# astable_multivibrator.net
KiCad netlist of a schematic drawn in EAGLE
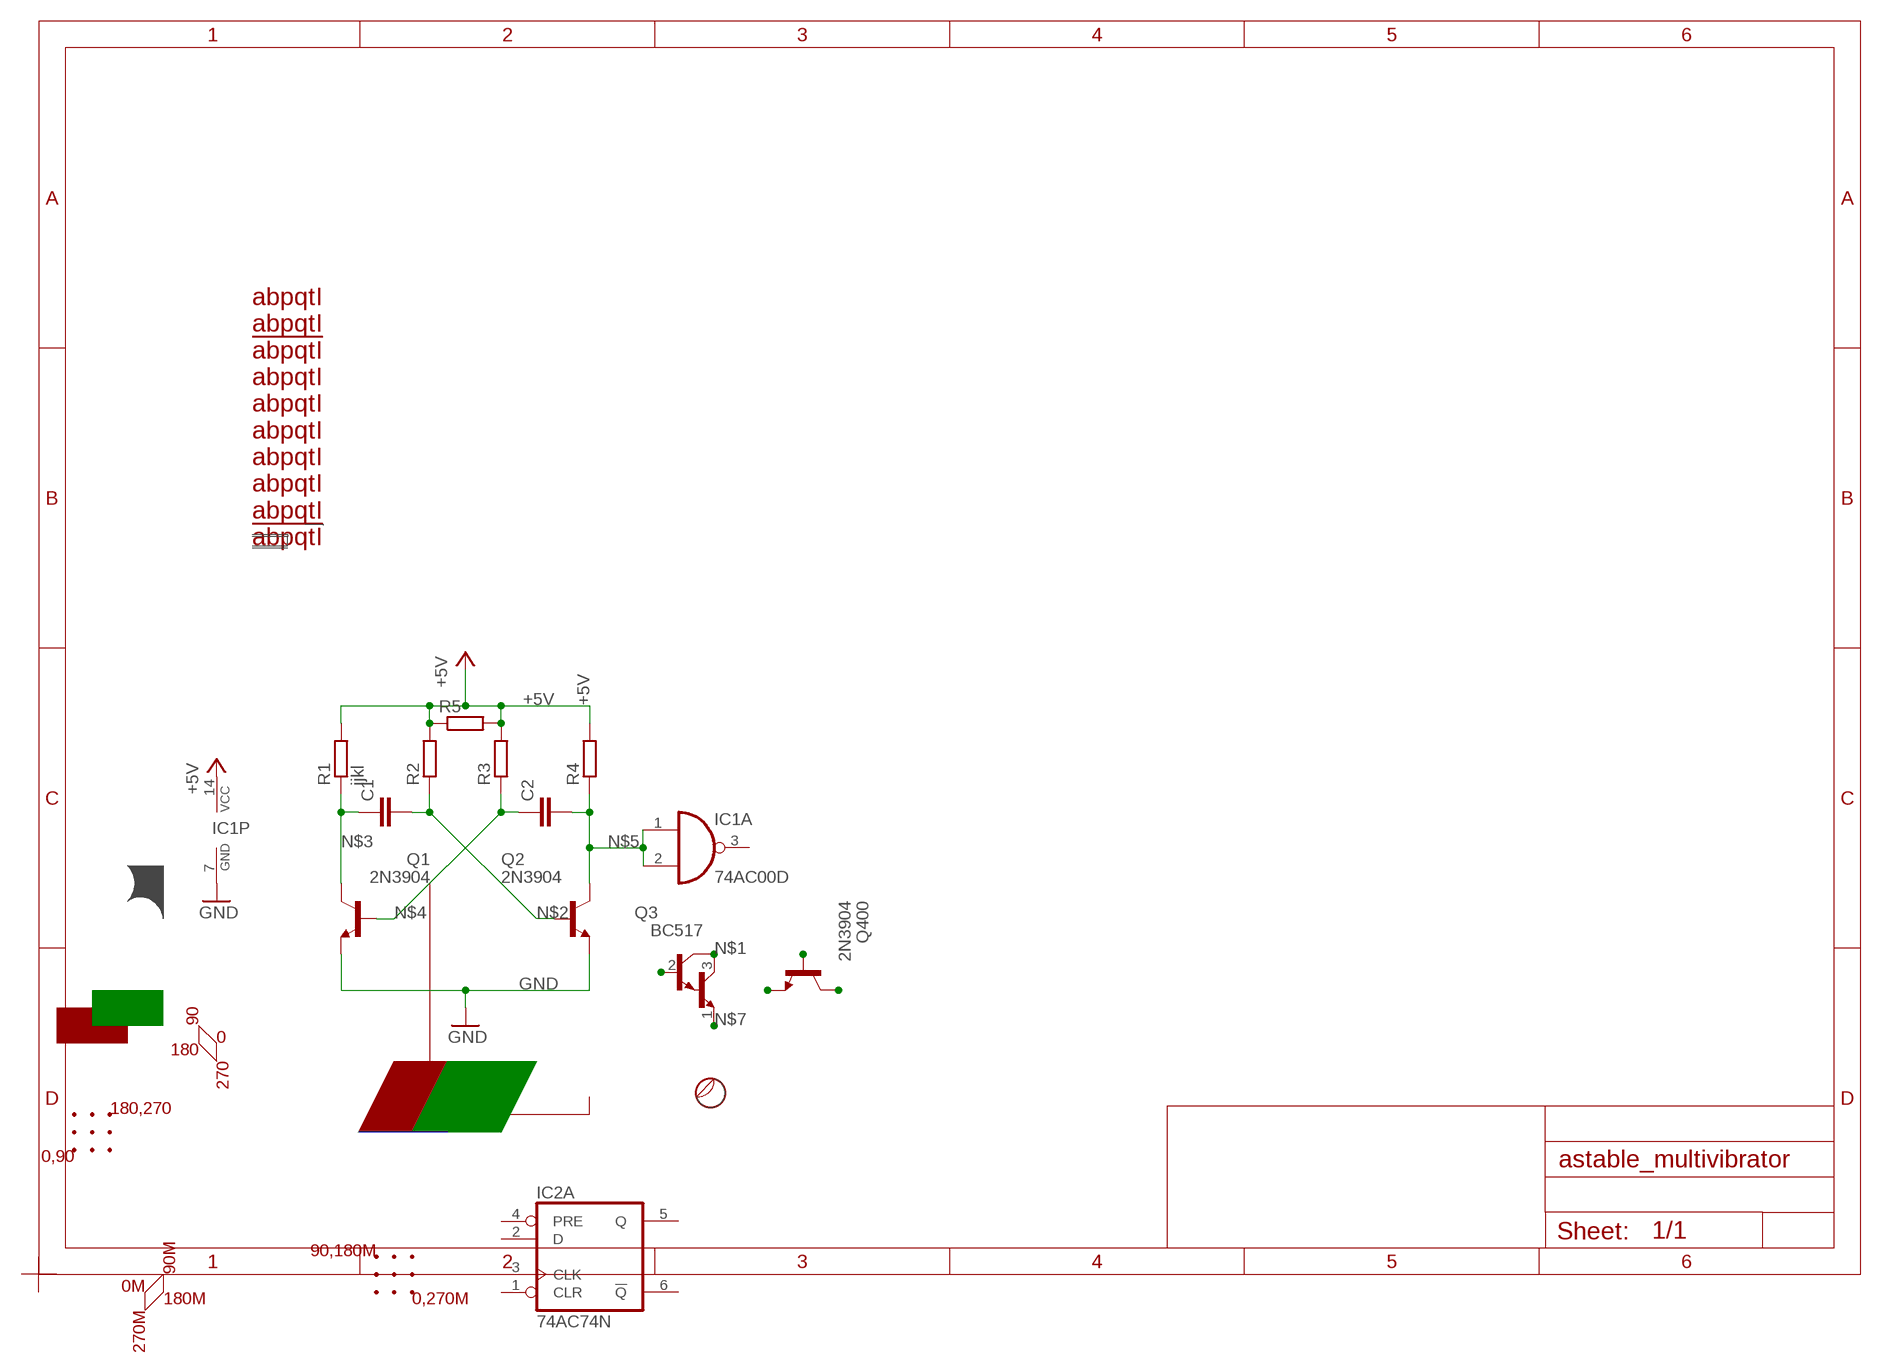
[diagram p0: schematic, sheet 1]

(export (version "E")
  (design (tool "Eeschema 10.0.6"))
  (components
    (comp (ref "C1")
      (value "C-EU025-024X044")
      (footprint "eagle-import:C025-024X044")
      (libsource (lib "eagle-import") (part "C-EU025-024X044"))
    )
    (comp (ref "C2")
      (value "C-EU025-024X044")
      (footprint "eagle-import:C025-024X044")
      (libsource (lib "eagle-import") (part "C-EU025-024X044"))
    )
    (comp (ref "IC1")
      (value "74AC00D")
      (footprint "eagle-import:SO14")
      (libsource (lib "eagle-import") (part "7400DAC"))
    )
    (comp (ref "IC2")
      (value "74AC74N")
      (footprint "eagle-import:DIL14")
      (libsource (lib "eagle-import") (part "7474NAC"))
    )
    (comp (ref "Q1")
      (value "2N3904")
      (footprint "eagle-import:TO92")
      (libsource (lib "eagle-import") (part "2N3904"))
    )
    (comp (ref "Q2")
      (value "2N3904")
      (footprint "eagle-import:TO92")
      (libsource (lib "eagle-import") (part "2N3904"))
    )
    (comp (ref "Q3")
      (value "BC517")
      (footprint "eagle-import:TO92")
      (libsource (lib "eagle-import") (part "BC517"))
    )
    (comp (ref "Q400")
      (value "2N3904")
      (footprint "eagle-import:TO92")
      (libsource (lib "eagle-import") (part "2N3904"))
    )
    (comp (ref "R1")
      (value "ijkl")
      (footprint "eagle-import:M2012")
      (libsource (lib "eagle-import") (part "R-EU_M2012"))
    )
    (comp (ref "R2")
      (value "R-EU_M2012")
      (footprint "eagle-import:M2012")
      (libsource (lib "eagle-import") (part "R-EU_M2012"))
    )
    (comp (ref "R3")
      (value "R-EU_M2012")
      (footprint "eagle-import:M2012")
      (libsource (lib "eagle-import") (part "R-EU_M2012"))
    )
    (comp (ref "R4")
      (value "R-EU_M2012")
      (footprint "eagle-import:M2012")
      (libsource (lib "eagle-import") (part "R-EU_M2012"))
    )
    (comp (ref "R5")
      (value "R-EU_M2012")
      (footprint "eagle-import:M2012")
      (libsource (lib "eagle-import") (part "R-EU_M2012"))
    )
  )
  (nets
    (net (code "1") (name "+5V") (class "Default")
      (node (ref "IC1") (pin "14") (pinfunction "VCC_14") (pintype "power_in"))
      (node (ref "R1") (pin "2") (pinfunction "2_2") (pintype "passive"))
      (node (ref "R2") (pin "2") (pinfunction "2_2") (pintype "passive"))
      (node (ref "R3") (pin "2") (pinfunction "2_2") (pintype "passive"))
      (node (ref "R4") (pin "2") (pinfunction "2_2") (pintype "passive"))
      (node (ref "R5") (pin "1") (pinfunction "1_1") (pintype "passive"))
      (node (ref "R5") (pin "2") (pinfunction "2_2") (pintype "passive"))
    )
    (net (code "2") (name "/N$1") (class "Default")
      (node (ref "Q3") (pin "3") (pinfunction "C_3") (pintype "passive"))
    )
    (net (code "3") (name "/N$2") (class "Default")
      (node (ref "C1") (pin "2") (pinfunction "2_2") (pintype "passive"))
      (node (ref "Q2") (pin "2") (pinfunction "B_2") (pintype "passive"))
      (node (ref "R2") (pin "1") (pinfunction "1_1") (pintype "passive"))
    )
    (net (code "4") (name "/N$3") (class "Default")
      (node (ref "C1") (pin "1") (pinfunction "1_1") (pintype "passive"))
      (node (ref "Q1") (pin "1") (pinfunction "C_1") (pintype "passive"))
      (node (ref "R1") (pin "1") (pinfunction "1_1") (pintype "passive"))
    )
    (net (code "5") (name "/N$4") (class "Default")
      (node (ref "C2") (pin "1") (pinfunction "1_1") (pintype "passive"))
      (node (ref "Q1") (pin "2") (pinfunction "B_2") (pintype "passive"))
      (node (ref "R3") (pin "1") (pinfunction "1_1") (pintype "passive"))
    )
    (net (code "6") (name "/N$5") (class "Default")
      (node (ref "C2") (pin "2") (pinfunction "2_2") (pintype "passive"))
      (node (ref "IC1") (pin "1") (pinfunction "I0_1") (pintype "input"))
      (node (ref "IC1") (pin "2") (pinfunction "I1_2") (pintype "input"))
      (node (ref "Q2") (pin "1") (pinfunction "C_1") (pintype "passive"))
      (node (ref "R4") (pin "1") (pinfunction "1_1") (pintype "passive"))
    )
    (net (code "7") (name "/N$7") (class "Default")
      (node (ref "Q3") (pin "1") (pinfunction "E_1") (pintype "passive"))
    )
    (net (code "8") (name "GND") (class "Default")
      (node (ref "IC1") (pin "7") (pinfunction "GND_7") (pintype "power_in"))
      (node (ref "Q1") (pin "3") (pinfunction "E_3") (pintype "passive"))
      (node (ref "Q2") (pin "3") (pinfunction "E_3") (pintype "passive"))
    )
    (net (code "9") (name "unconnected-(IC1A-O-Pad3)") (class "Default")
      (node (ref "IC1") (pin "3") (pinfunction "O_3") (pintype "output"))
    )
    (net (code "10") (name "unconnected-(IC2A-CLK-Pad3)") (class "Default")
      (node (ref "IC2") (pin "3") (pinfunction "CLK_3") (pintype "input"))
    )
    (net (code "11") (name "unconnected-(IC2A-CLR-Pad1)") (class "Default")
      (node (ref "IC2") (pin "1") (pinfunction "CLR_1") (pintype "input"))
    )
    (net (code "12") (name "unconnected-(IC2A-D-Pad2)") (class "Default")
      (node (ref "IC2") (pin "2") (pinfunction "D_2") (pintype "input"))
    )
    (net (code "13") (name "unconnected-(IC2A-PRE-Pad4)") (class "Default")
      (node (ref "IC2") (pin "4") (pinfunction "PRE_4") (pintype "input"))
    )
    (net (code "14") (name "unconnected-(IC2A-Q-Pad5)") (class "Default")
      (node (ref "IC2") (pin "5") (pinfunction "Q_5") (pintype "output"))
    )
    (net (code "15") (name "unconnected-(IC2A-~{Q}-Pad6)") (class "Default")
      (node (ref "IC2") (pin "6") (pinfunction "~{Q}_6") (pintype "output"))
    )
    (net (code "16") (name "unconnected-(Q3-B-Pad2)") (class "Default")
      (node (ref "Q3") (pin "2") (pinfunction "B_2") (pintype "passive"))
    )
    (net (code "17") (name "unconnected-(Q400-B-Pad2)") (class "Default")
      (node (ref "Q400") (pin "2") (pinfunction "B_2") (pintype "passive"))
    )
    (net (code "18") (name "unconnected-(Q400-C-Pad1)") (class "Default")
      (node (ref "Q400") (pin "1") (pinfunction "C_1") (pintype "passive"))
    )
    (net (code "19") (name "unconnected-(Q400-E-Pad3)") (class "Default")
      (node (ref "Q400") (pin "3") (pinfunction "E_3") (pintype "passive"))
    )
  )
)
